# 1-Schematic_LABBOX_V3_Starting_point.net
KiCad netlist of a schematic drawn in EasyEDA
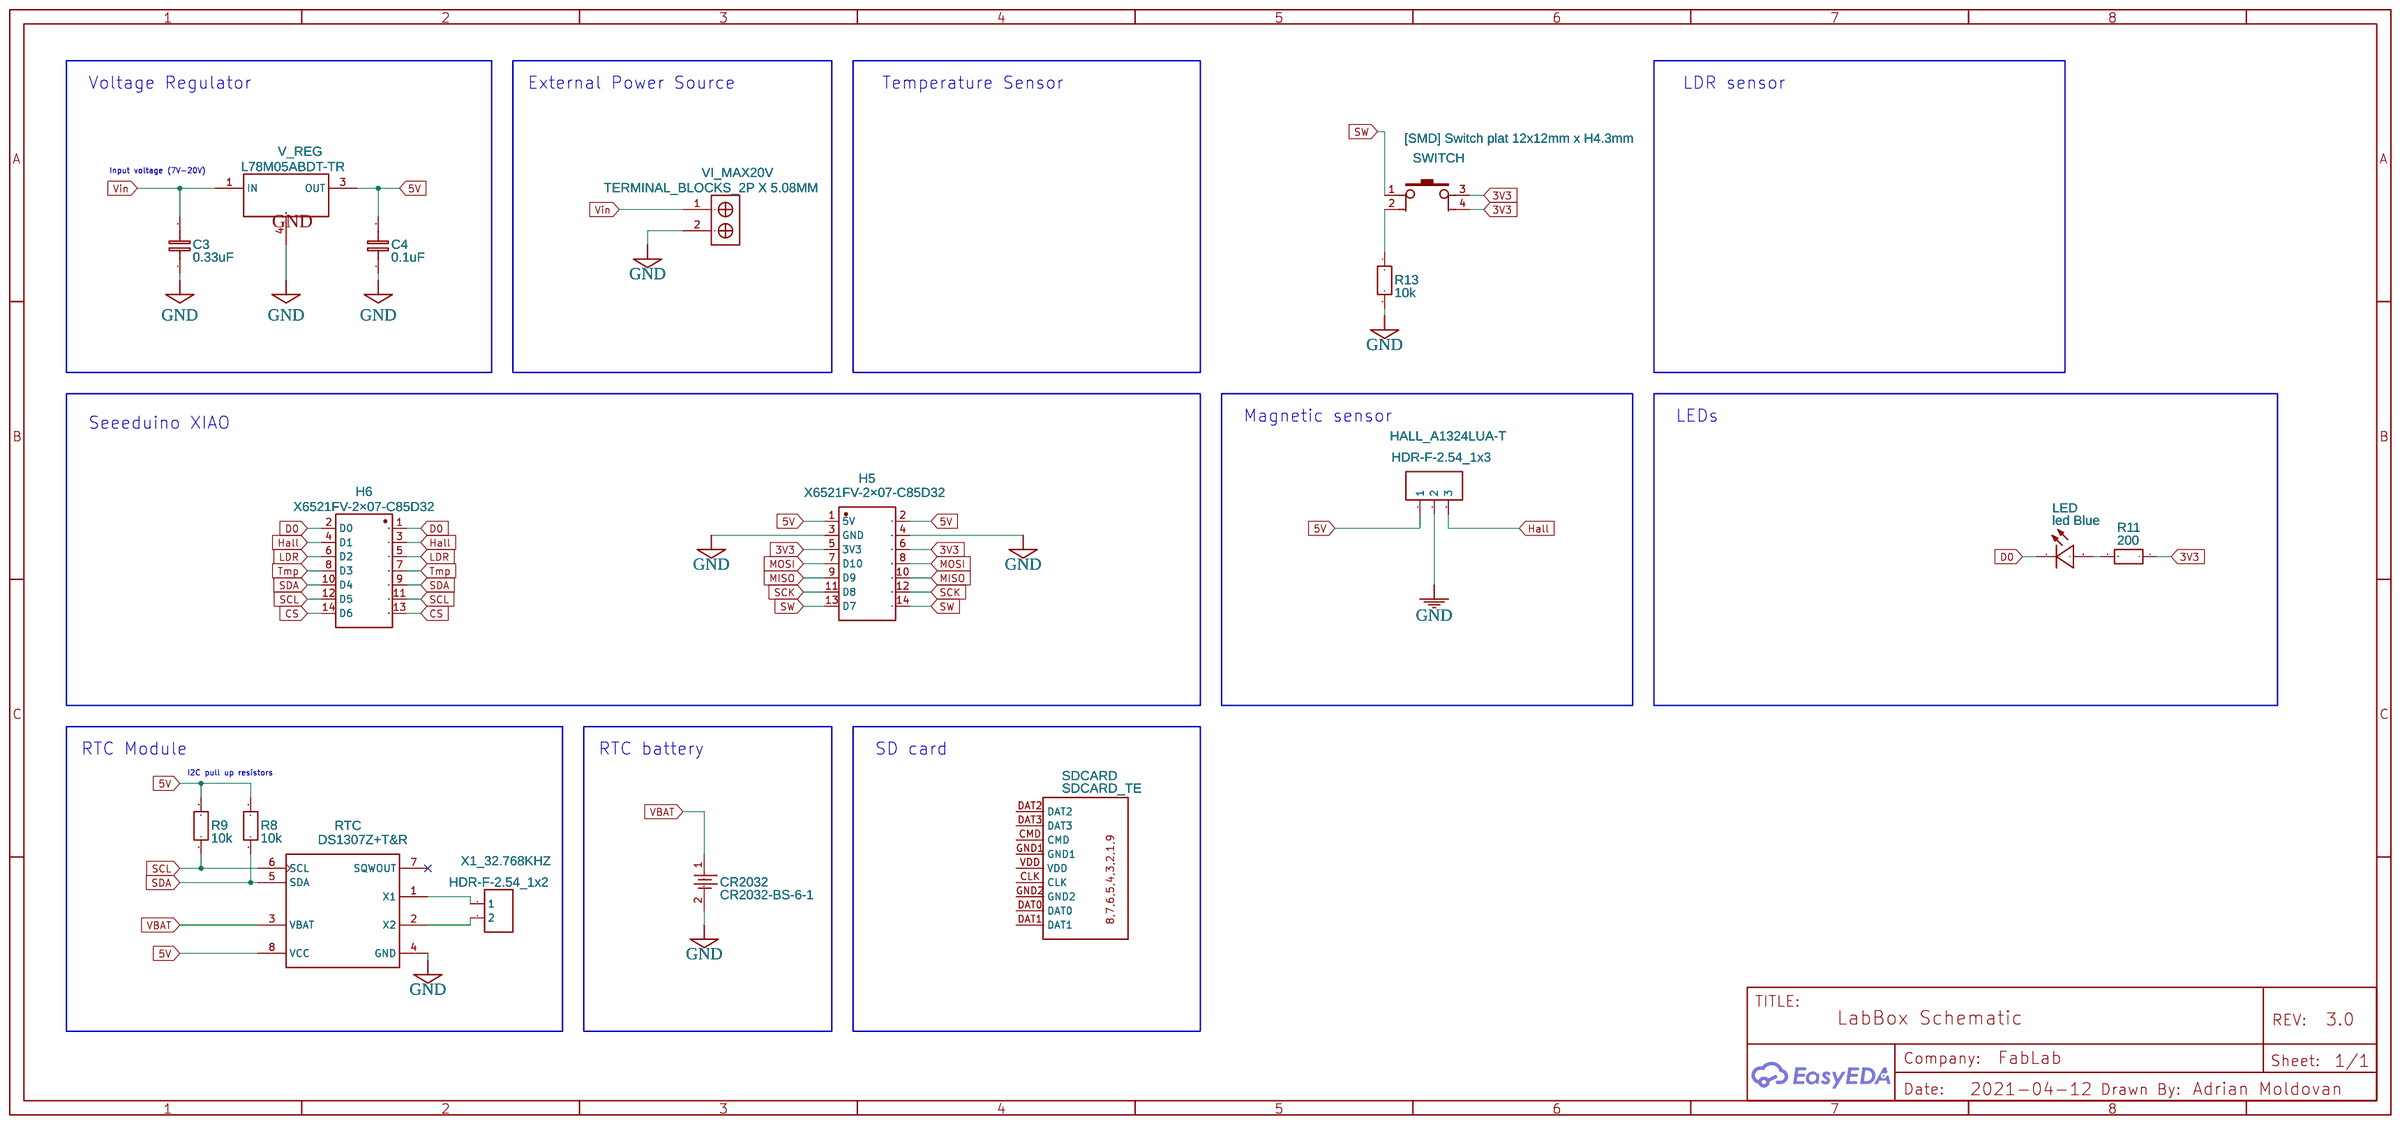
[diagram p0: schematic sheet]

(export (version "E")
  (design (tool "Eeschema 10.0.6"))
  (components
    (comp (ref "C3") (value "0.33uF") (libsource (lib "") (part "C_1206_EU_1")))
    (comp (ref "C4") (value "0.1uF") (libsource (lib "") (part "C_1206_EU")))
    (comp (ref "CR2032")
      (value "CR2032-BS-6-1")
      (fields (field (name "BOM_Supplier Part") "C70377"))
      (libsource (lib "") (part "CR2032-BS-6-1"))
    )
    (comp (ref "H5")
      (value "X6521FV-2×07-C85D32")
      (fields (field (name "BOM_Supplier Part") "C718229"))
      (libsource (lib "") (part "X6521FV-2×07-C85D32"))
    )
    (comp (ref "H6")
      (value "X6521FV-2×07-C85D32")
      (fields (field (name "BOM_Supplier Part") "C718229"))
      (libsource (lib "") (part "X6521FV-2×07-C85D32_1"))
    )
    (comp (ref "HALL_A1324LUA-T")
      (value "HDR-F-2.54_1x3")
      (fields (field (name "BOM_Supplier Part") "C146690"))
      (libsource (lib "") (part "HDR-F-2.54_1x3"))
    )
    (comp (ref "LED")
      (value "led Blue")
      (fields (field (name "BOM_Manufacturer Part") "led Green") (field (name "BOM_Supplier Part") "C14641"))
      (libsource (lib "") (part "led Green"))
    )
    (comp (ref "R8") (value "10k") (libsource (lib "") (part "R_1206_EU_1")))
    (comp (ref "R9") (value "10k") (libsource (lib "") (part "R_1206_EU_1")))
    (comp (ref "R11") (value "200") (libsource (lib "") (part "R_1206_EU")))
    (comp (ref "R13") (value "10k") (libsource (lib "") (part "R_1206_EU_2")))
    (comp (ref "RTC")
      (value "DS1307Z+T&R")
      (fields (field (name "BOM_Supplier Part") "C9868"))
      (libsource (lib "") (part "DS1307Z+T&amp;amp;R"))
    )
    (comp (ref "SDCARD") (value "SDCARD_TE") (libsource (lib "") (part "SDCARD_TE")))
    (comp (ref "SWITCH")
      (value "[SMD] Switch plat 12x12mm x H4.3mm")
      (fields (field (name "BOM_Supplier Part") "C410376"))
      (libsource (lib "") (part "[SMD] Switch plat 12x12mm x H4.3mm"))
    )
    (comp (ref "VI_MAX20V")
      (value "TERMINAL_BLOCKS_2P X 5.08MM")
      (fields
        (field (name "BOM_Manufacturer Part") "Terminal Block")
        (field (name "BOM_Supplier Part") "undefined")
      )
      (libsource (lib "") (part "TERMINAL_BLOCKS_2P X 5.08MM"))
    )
    (comp (ref "V_REG")
      (value "L78M05ABDT-TR")
      (fields (field (name "BOM_Supplier Part") "C58069"))
      (libsource (lib "") (part "L78M05ABDT-TR"))
    )
    (comp (ref "X1_32.768KHZ")
      (value "HDR-F-2.54_1x2")
      (fields (field (name "BOM_Supplier Part") "C49661"))
      (libsource (lib "") (part "HDR-F-2.54_1x2"))
    )
  )
  (nets
    (net (code "1") (name "3V3") (class "Default")
      (node (ref "H5") (pin "5") (pinfunction "3V3_5") (pintype "unspecified"))
      (node (ref "H5") (pin "6") (pinfunction "3V3_6") (pintype "unspecified"))
      (node (ref "R11") (pin "1") (pinfunction "1_1") (pintype "unspecified"))
      (node (ref "SWITCH") (pin "3") (pinfunction "3_3") (pintype "input"))
      (node (ref "SWITCH") (pin "4") (pinfunction "4_4") (pintype "input"))
    )
    (net (code "2") (name "5V") (class "Default")
      (node (ref "C4") (pin "2") (pinfunction "2_2") (pintype "unspecified"))
      (node (ref "H5") (pin "1") (pinfunction "5V_1") (pintype "unspecified"))
      (node (ref "H5") (pin "2") (pinfunction "5V_2") (pintype "unspecified"))
      (node (ref "HALL_A1324LUA-T") (pin "1") (pinfunction "1_1") (pintype "input"))
      (node (ref "R8") (pin "2") (pinfunction "2_2") (pintype "unspecified"))
      (node (ref "R9") (pin "2") (pinfunction "2_2") (pintype "unspecified"))
      (node (ref "RTC") (pin "8") (pinfunction "VCC_8") (pintype "passive"))
      (node (ref "V_REG") (pin "3") (pinfunction "OUT_3") (pintype "passive"))
    )
    (net (code "3") (name "CS") (class "Default")
      (node (ref "H6") (pin "13") (pinfunction "D6_13") (pintype "unspecified"))
      (node (ref "H6") (pin "14") (pinfunction "D6_14") (pintype "unspecified"))
    )
    (net (code "4") (name "D0") (class "Default")
      (node (ref "H6") (pin "1") (pinfunction "D0_1") (pintype "unspecified"))
      (node (ref "H6") (pin "2") (pinfunction "D0_2") (pintype "unspecified"))
      (node (ref "LED") (pin "1") (pinfunction "-_1") (pintype "unspecified"))
    )
    (net (code "5") (name "GND") (class "Default")
      (node (ref "C3") (pin "1") (pinfunction "1_1") (pintype "unspecified"))
      (node (ref "C4") (pin "1") (pinfunction "1_1") (pintype "unspecified"))
      (node (ref "CR2032") (pin "2") (pinfunction "2_2") (pintype "input"))
      (node (ref "H5") (pin "3") (pinfunction "GND_3") (pintype "unspecified"))
      (node (ref "H5") (pin "4") (pinfunction "GND_4") (pintype "unspecified"))
      (node (ref "HALL_A1324LUA-T") (pin "2") (pinfunction "2_2") (pintype "input"))
      (node (ref "R13") (pin "2") (pinfunction "2_2") (pintype "unspecified"))
      (node (ref "RTC") (pin "4") (pinfunction "GND_4") (pintype "passive"))
      (node (ref "VI_MAX20V") (pin "2") (pinfunction "2_2") (pintype "unspecified"))
      (node (ref "V_REG") (pin "4") (pinfunction "GND_4") (pintype "passive"))
    )
    (net (code "6") (name "Hall") (class "Default")
      (node (ref "H6") (pin "3") (pinfunction "D1_3") (pintype "unspecified"))
      (node (ref "H6") (pin "4") (pinfunction "D1_4") (pintype "unspecified"))
      (node (ref "HALL_A1324LUA-T") (pin "3") (pinfunction "3_3") (pintype "input"))
    )
    (net (code "7") (name "LDR") (class "Default")
      (node (ref "H6") (pin "5") (pinfunction "D2_5") (pintype "unspecified"))
      (node (ref "H6") (pin "6") (pinfunction "D2_6") (pintype "unspecified"))
    )
    (net (code "8") (name "MISO") (class "Default")
      (node (ref "H5") (pin "10") (pinfunction "D9_10") (pintype "unspecified"))
      (node (ref "H5") (pin "9") (pinfunction "D9_9") (pintype "unspecified"))
    )
    (net (code "9") (name "MOSI") (class "Default")
      (node (ref "H5") (pin "7") (pinfunction "D10_7") (pintype "unspecified"))
      (node (ref "H5") (pin "8") (pinfunction "D10_8") (pintype "unspecified"))
    )
    (net (code "10") (name "Net-(LED-+)") (class "Default")
      (node (ref "LED") (pin "2") (pinfunction "+_2") (pintype "unspecified"))
      (node (ref "R11") (pin "2") (pinfunction "2_2") (pintype "unspecified"))
    )
    (net (code "11") (name "Net-(R13-Pad1)") (class "Default")
      (node (ref "R13") (pin "1") (pinfunction "1_1") (pintype "unspecified"))
      (node (ref "SWITCH") (pin "2") (pinfunction "2_2") (pintype "input"))
    )
    (net (code "12") (name "Net-(RTC-X1)") (class "Default")
      (node (ref "RTC") (pin "1") (pinfunction "X1_1") (pintype "unspecified"))
      (node (ref "X1_32.768KHZ") (pin "1") (pinfunction "1_1") (pintype "input"))
    )
    (net (code "13") (name "Net-(RTC-X2)") (class "Default")
      (node (ref "RTC") (pin "2") (pinfunction "X2_2") (pintype "unspecified"))
      (node (ref "X1_32.768KHZ") (pin "2") (pinfunction "2_2") (pintype "input"))
    )
    (net (code "14") (name "SCK") (class "Default")
      (node (ref "H5") (pin "11") (pinfunction "D8_11") (pintype "unspecified"))
      (node (ref "H5") (pin "12") (pinfunction "D8_12") (pintype "unspecified"))
    )
    (net (code "15") (name "SCL") (class "Default")
      (node (ref "H6") (pin "11") (pinfunction "D5_11") (pintype "unspecified"))
      (node (ref "H6") (pin "12") (pinfunction "D5_12") (pintype "unspecified"))
      (node (ref "R9") (pin "1") (pinfunction "1_1") (pintype "unspecified"))
      (node (ref "RTC") (pin "6") (pinfunction "SCL_6") (pintype "unspecified"))
    )
    (net (code "16") (name "SDA") (class "Default")
      (node (ref "H6") (pin "10") (pinfunction "D4_10") (pintype "unspecified"))
      (node (ref "H6") (pin "9") (pinfunction "D4_9") (pintype "unspecified"))
      (node (ref "R8") (pin "1") (pinfunction "1_1") (pintype "unspecified"))
      (node (ref "RTC") (pin "5") (pinfunction "SDA_5") (pintype "bidirectional"))
    )
    (net (code "17") (name "SW") (class "Default")
      (node (ref "H5") (pin "13") (pinfunction "D7_13") (pintype "unspecified"))
      (node (ref "H5") (pin "14") (pinfunction "14_14") (pintype "unspecified"))
      (node (ref "SWITCH") (pin "1") (pinfunction "1_1") (pintype "input"))
    )
    (net (code "18") (name "Tmp") (class "Default")
      (node (ref "H6") (pin "7") (pinfunction "D3_7") (pintype "unspecified"))
      (node (ref "H6") (pin "8") (pinfunction "D3_8") (pintype "unspecified"))
    )
    (net (code "19") (name "VBAT") (class "Default")
      (node (ref "CR2032") (pin "1") (pinfunction "1_1") (pintype "input"))
      (node (ref "RTC") (pin "3") (pinfunction "VBAT_3") (pintype "passive"))
    )
    (net (code "20") (name "Vin") (class "Default")
      (node (ref "C3") (pin "2") (pinfunction "2_2") (pintype "unspecified"))
      (node (ref "VI_MAX20V") (pin "1") (pinfunction "1_1") (pintype "unspecified"))
      (node (ref "V_REG") (pin "1") (pinfunction "IN_1") (pintype "passive"))
    )
    (net (code "21") (name "unconnected-(RTC-SQWOUT-Pad7)") (class "Default")
      (node (ref "RTC") (pin "7") (pinfunction "SQWOUT_7") (pintype "unspecified+no_connect"))
    )
    (net (code "22") (name "unconnected-(SDCARD-PadCLK)") (class "Default")
      (node (ref "SDCARD") (pin "CLK") (pinfunction "CLK_CLK") (pintype "bidirectional"))
    )
    (net (code "23") (name "unconnected-(SDCARD-PadCMD)") (class "Default")
      (node (ref "SDCARD") (pin "CMD") (pinfunction "CMD_CMD") (pintype "bidirectional"))
    )
    (net (code "24") (name "unconnected-(SDCARD-PadDAT0)") (class "Default")
      (node (ref "SDCARD") (pin "DAT0") (pinfunction "DAT0_DAT0") (pintype "bidirectional"))
    )
    (net (code "25") (name "unconnected-(SDCARD-PadDAT1)") (class "Default")
      (node (ref "SDCARD") (pin "DAT1") (pinfunction "DAT1_DAT1") (pintype "bidirectional"))
    )
    (net (code "26") (name "unconnected-(SDCARD-PadDAT2)") (class "Default")
      (node (ref "SDCARD") (pin "DAT2") (pinfunction "DAT2_DAT2") (pintype "bidirectional"))
    )
    (net (code "27") (name "unconnected-(SDCARD-PadDAT3)") (class "Default")
      (node (ref "SDCARD") (pin "DAT3") (pinfunction "DAT3_DAT3") (pintype "bidirectional"))
    )
    (net (code "28") (name "unconnected-(SDCARD-PadGND1)") (class "Default")
      (node (ref "SDCARD") (pin "GND1") (pinfunction "GND1_GND1") (pintype "bidirectional"))
    )
    (net (code "29") (name "unconnected-(SDCARD-PadGND2)") (class "Default")
      (node (ref "SDCARD") (pin "GND2") (pinfunction "GND2_GND2") (pintype "bidirectional"))
    )
    (net (code "30") (name "unconnected-(SDCARD-PadVDD)") (class "Default")
      (node (ref "SDCARD") (pin "VDD") (pinfunction "VDD_VDD") (pintype "bidirectional"))
    )
  )
)
